# RN42.net
KiCad netlist of a schematic drawn in EAGLE
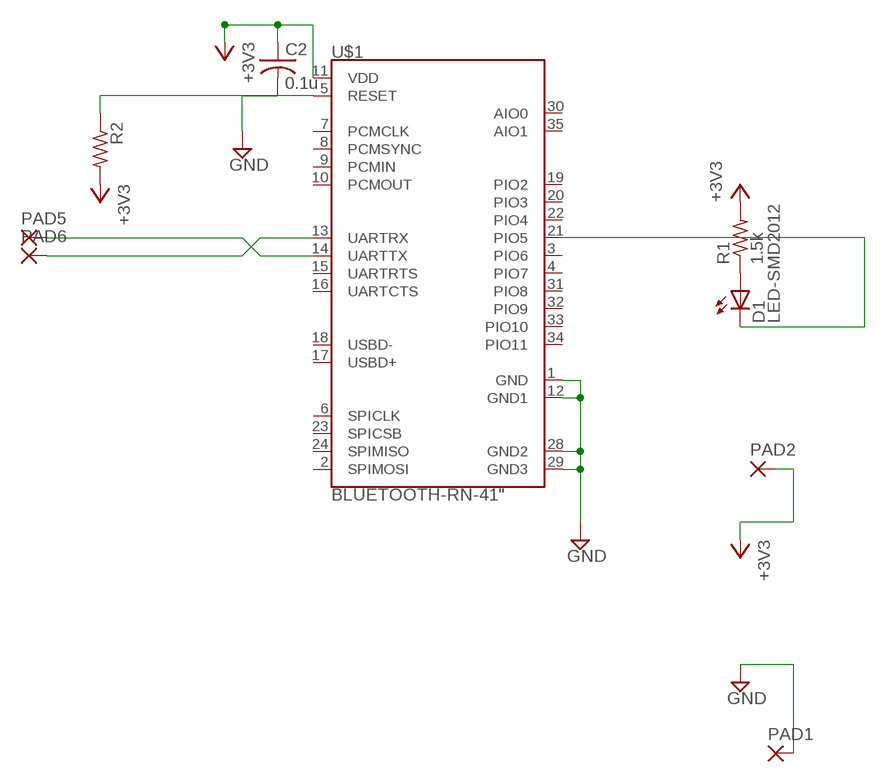
[diagram p0: schematic, sheet 1]

(export (version "E")
  (design (tool "Eeschema 10.0.6"))
  (components
    (comp (ref "C2")
      (value "0.1u")
      (footprint "eagle-import:2012-C")
      (libsource (lib "eagle-import") (part "C-2012"))
    )
    (comp (ref "D1")
      (value "LED-SMD2012")
      (footprint "eagle-import:D2012")
      (libsource (lib "eagle-import") (part "LED-SMD2012"))
    )
    (comp (ref "PAD1")
      (value "SMD5")
      (footprint "eagle-import:SMD2,54-5,08")
      (libsource (lib "eagle-import") (part "SMD5"))
    )
    (comp (ref "PAD2")
      (value "SMD5")
      (footprint "eagle-import:SMD2,54-5,08")
      (libsource (lib "eagle-import") (part "SMD5"))
    )
    (comp (ref "PAD5")
      (value "SMD5")
      (footprint "eagle-import:SMD2,54-5,08")
      (libsource (lib "eagle-import") (part "SMD5"))
    )
    (comp (ref "PAD6")
      (value "SMD5")
      (footprint "eagle-import:SMD2,54-5,08")
      (libsource (lib "eagle-import") (part "SMD5"))
    )
    (comp (ref "R1")
      (value "1.5k")
      (footprint "eagle-import:2012-R")
      (libsource (lib "eagle-import") (part "R-2012"))
    )
    (comp (ref "R2")
      (value "10k")
      (footprint "eagle-import:2012-R")
      (libsource (lib "eagle-import") (part "R-2012"))
    )
    (comp (ref "U$1")
      (value "BLUETOOTH-RN-41\"")
      (footprint "eagle-import:RN41")
      (libsource (lib "eagle-import") (part "BLUETOOTH-RN-41{dblquote}"))
    )
  )
  (nets
    (net (code "1") (name "+3V3") (class "Default")
      (node (ref "C2") (pin "1") (pinfunction "1_1") (pintype "passive"))
      (node (ref "PAD2") (pin "1") (pinfunction "P_1") (pintype "passive"))
      (node (ref "R1") (pin "2") (pinfunction "2_2") (pintype "passive"))
      (node (ref "R2") (pin "2") (pinfunction "2_2") (pintype "passive"))
      (node (ref "U$1") (pin "11") (pinfunction "VDD_11") (pintype "bidirectional"))
    )
    (net (code "2") (name "GND") (class "Default")
      (node (ref "C2") (pin "2") (pinfunction "2_2") (pintype "passive"))
      (node (ref "PAD1") (pin "1") (pinfunction "P_1") (pintype "passive"))
      (node (ref "U$1") (pin "1") (pinfunction "GND_1") (pintype "bidirectional"))
      (node (ref "U$1") (pin "12") (pinfunction "GND1_12") (pintype "bidirectional"))
      (node (ref "U$1") (pin "28") (pinfunction "GND2_28") (pintype "bidirectional"))
      (node (ref "U$1") (pin "29") (pinfunction "GND3_29") (pintype "bidirectional"))
    )
    (net (code "3") (name "Net-(D1-PadA)") (class "Default")
      (node (ref "D1") (pin "A") (pinfunction "A_A") (pintype "passive"))
      (node (ref "R1") (pin "1") (pinfunction "1_1") (pintype "passive"))
    )
    (net (code "4") (name "Net-(PAD5-P)") (class "Default")
      (node (ref "PAD5") (pin "1") (pinfunction "P_1") (pintype "passive"))
      (node (ref "U$1") (pin "14") (pinfunction "UARTTX_14") (pintype "bidirectional"))
    )
    (net (code "5") (name "Net-(PAD6-P)") (class "Default")
      (node (ref "PAD6") (pin "1") (pinfunction "P_1") (pintype "passive"))
      (node (ref "U$1") (pin "13") (pinfunction "UARTRX_13") (pintype "bidirectional"))
    )
    (net (code "6") (name "Net-(U$1-PIO5)") (class "Default")
      (node (ref "D1") (pin "K") (pinfunction "K_K") (pintype "passive"))
      (node (ref "U$1") (pin "21") (pinfunction "PIO5_21") (pintype "bidirectional"))
    )
    (net (code "7") (name "Net-(U$1-RESET)") (class "Default")
      (node (ref "R2") (pin "1") (pinfunction "1_1") (pintype "passive"))
      (node (ref "U$1") (pin "5") (pinfunction "RESET_5") (pintype "bidirectional"))
    )
    (net (code "8") (name "unconnected-(U$1-AIO0-Pad30)") (class "Default")
      (node (ref "U$1") (pin "30") (pinfunction "AIO0_30") (pintype "bidirectional"))
    )
    (net (code "9") (name "unconnected-(U$1-AIO1-Pad35)") (class "Default")
      (node (ref "U$1") (pin "35") (pinfunction "AIO1_35") (pintype "bidirectional"))
    )
    (net (code "10") (name "unconnected-(U$1-PCMCLK-Pad7)") (class "Default")
      (node (ref "U$1") (pin "7") (pinfunction "PCMCLK_7") (pintype "bidirectional"))
    )
    (net (code "11") (name "unconnected-(U$1-PCMIN-Pad9)") (class "Default")
      (node (ref "U$1") (pin "9") (pinfunction "PCMIN_9") (pintype "bidirectional"))
    )
    (net (code "12") (name "unconnected-(U$1-PCMOUT-Pad10)") (class "Default")
      (node (ref "U$1") (pin "10") (pinfunction "PCMOUT_10") (pintype "bidirectional"))
    )
    (net (code "13") (name "unconnected-(U$1-PCMSYNC-Pad8)") (class "Default")
      (node (ref "U$1") (pin "8") (pinfunction "PCMSYNC_8") (pintype "bidirectional"))
    )
    (net (code "14") (name "unconnected-(U$1-PIO2-Pad19)") (class "Default")
      (node (ref "U$1") (pin "19") (pinfunction "PIO2_19") (pintype "bidirectional"))
    )
    (net (code "15") (name "unconnected-(U$1-PIO3-Pad20)") (class "Default")
      (node (ref "U$1") (pin "20") (pinfunction "PIO3_20") (pintype "bidirectional"))
    )
    (net (code "16") (name "unconnected-(U$1-PIO4-Pad22)") (class "Default")
      (node (ref "U$1") (pin "22") (pinfunction "PIO4_22") (pintype "bidirectional"))
    )
    (net (code "17") (name "unconnected-(U$1-PIO6-Pad3)") (class "Default")
      (node (ref "U$1") (pin "3") (pinfunction "PIO6_3") (pintype "bidirectional"))
    )
    (net (code "18") (name "unconnected-(U$1-PIO7-Pad4)") (class "Default")
      (node (ref "U$1") (pin "4") (pinfunction "PIO7_4") (pintype "bidirectional"))
    )
    (net (code "19") (name "unconnected-(U$1-PIO8-Pad31)") (class "Default")
      (node (ref "U$1") (pin "31") (pinfunction "PIO8_31") (pintype "bidirectional"))
    )
    (net (code "20") (name "unconnected-(U$1-PIO9-Pad32)") (class "Default")
      (node (ref "U$1") (pin "32") (pinfunction "PIO9_32") (pintype "bidirectional"))
    )
    (net (code "21") (name "unconnected-(U$1-PIO10-Pad33)") (class "Default")
      (node (ref "U$1") (pin "33") (pinfunction "PIO10_33") (pintype "bidirectional"))
    )
    (net (code "22") (name "unconnected-(U$1-PIO11-Pad34)") (class "Default")
      (node (ref "U$1") (pin "34") (pinfunction "PIO11_34") (pintype "bidirectional"))
    )
    (net (code "23") (name "unconnected-(U$1-SPICLK-Pad6)") (class "Default")
      (node (ref "U$1") (pin "6") (pinfunction "SPICLK_6") (pintype "bidirectional"))
    )
    (net (code "24") (name "unconnected-(U$1-SPICSB-Pad23)") (class "Default")
      (node (ref "U$1") (pin "23") (pinfunction "SPICSB_23") (pintype "bidirectional"))
    )
    (net (code "25") (name "unconnected-(U$1-SPIMISO-Pad24)") (class "Default")
      (node (ref "U$1") (pin "24") (pinfunction "SPIMISO_24") (pintype "bidirectional"))
    )
    (net (code "26") (name "unconnected-(U$1-SPIMOSI-Pad2)") (class "Default")
      (node (ref "U$1") (pin "2") (pinfunction "SPIMOSI_2") (pintype "bidirectional"))
    )
    (net (code "27") (name "unconnected-(U$1-UARTCTS-Pad16)") (class "Default")
      (node (ref "U$1") (pin "16") (pinfunction "UARTCTS_16") (pintype "bidirectional"))
    )
    (net (code "28") (name "unconnected-(U$1-UARTRTS-Pad15)") (class "Default")
      (node (ref "U$1") (pin "15") (pinfunction "UARTRTS_15") (pintype "bidirectional"))
    )
    (net (code "29") (name "unconnected-(U$1-USBD+-Pad17)") (class "Default")
      (node (ref "U$1") (pin "17") (pinfunction "USBD+_17") (pintype "bidirectional"))
    )
    (net (code "30") (name "unconnected-(U$1-USBD--Pad18)") (class "Default")
      (node (ref "U$1") (pin "18") (pinfunction "USBD-_18") (pintype "bidirectional"))
    )
  )
)
